# LightBoard_v1_0.net
KiCad netlist of a schematic drawn in Altium Designer
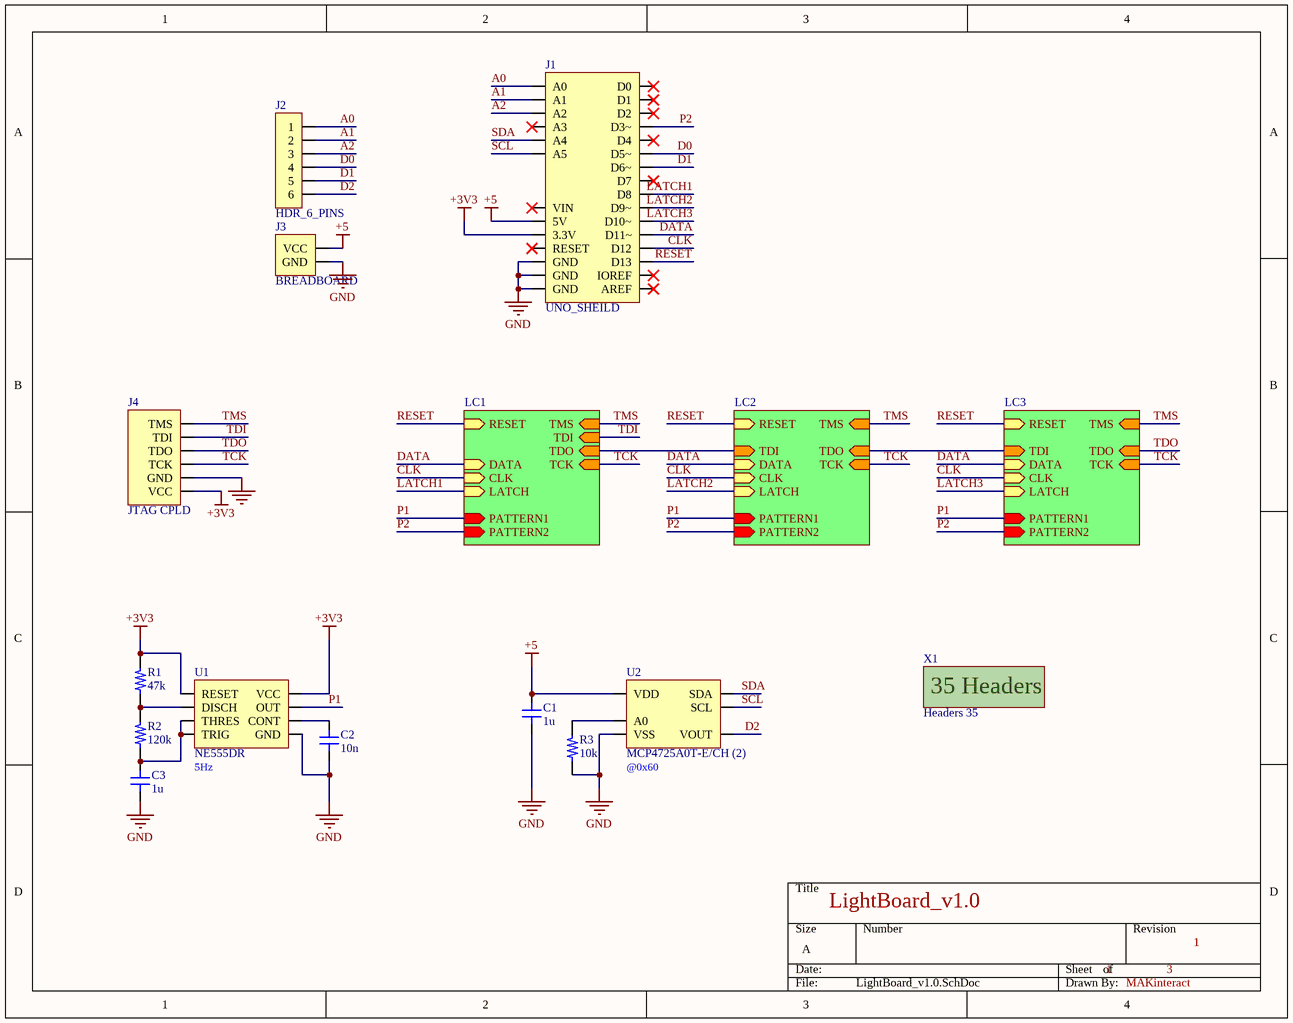
[diagram p0: LightBoard_v1.0.SchDoc]

(export (version "E")
  (design (tool "Eeschema 10.0.6"))
  (components
    (comp (ref "C1")
      (value "1u")
      (fields
        (field (name "MANUFACTURER") "Yageo")
        (field (name "MANUFACTURER PART NUMBER") "CC0805ZRY5V8BB105")
        (field (name "TOLERANCE") "80%")
      )
      (libsource (lib "LightBoard_v1.0") (part "C0805_1u"))
    )
    (comp (ref "C2")
      (value "10n")
      (description "Cap Ceramic 0.01uF 10V X7R 10% SMD 0402 125C Paper T/R")
      (fields
        (field (name "MANUFACTURER") "Yageo")
        (field (name "MANUFACTURER PART NUMBER") "CC0402KRX7R6BB103")
      )
      (libsource (lib "LightBoard_v1.0") (part "C0402_10n"))
    )
    (comp (ref "C3")
      (value "1u")
      (fields
        (field (name "MANUFACTURER") "Yageo")
        (field (name "MANUFACTURER PART NUMBER") "CC0805ZRY5V8BB105")
        (field (name "TOLERANCE") "80%")
      )
      (libsource (lib "LightBoard_v1.0") (part "C0805_1u"))
    )
    (comp (ref "J1")
      (value "UNO_SHEILD")
      (footprint "ARDUINO_UNO_SHIELD")
      (description "Arduino UNO shield")
      (fields (field (name "MANUFACTURER") "Arduino") (field (name "MANUFACTURER PART NUMBER") "A000073"))
      (libsource (lib "LightBoard_v1.0") (part "ARDUINO_UNO_SHIELD"))
    )
    (comp (ref "J2")
      (value "HDR_6_PINS")
      (description "Sockets to connect to Arduino pins")
      (libsource (lib "LightBoard_v1.0") (part "H_ARDUPINS"))
    )
    (comp (ref "J3")
      (value "BREADBOARD")
      (description "26*2 ROWS")
      (libsource (lib "LightBoard_v1.0") (part "BREADBOARD"))
    )
    (comp (ref "J4")
      (value "JTAG CPLD")
      (description "Socket to connect to JTAG")
      (libsource (lib "LightBoard_v1.0") (part "H_JTAG"))
    )
    (comp (ref "R1")
      (value "47k")
      (fields
        (field (name "MANUFACTURER") "Yageo")
        (field (name "MANUFACTURER PART NUMBER") "RC0402JR-0747KL")
        (field (name "TOLERANCE") "5%")
      )
      (libsource (lib "LightBoard_v1.0") (part "R0402_47K"))
    )
    (comp (ref "R2")
      (value "120k")
      (description "RES SMD 120K OHM 5% 1/16W 0402")
      (fields
        (field (name "MANUFACTURER") "Yageo")
        (field (name "MANUFACTURER PART NUMBER") "RC0402JR-07120KL")
      )
      (libsource (lib "LightBoard_v1.0") (part "R0402_120K"))
    )
    (comp (ref "R3")
      (value "10k")
      (description "RES SMD 10K OHM 1% 1/16W 0402")
      (fields
        (field (name "MANUFACTURER") "Yageo")
        (field (name "MANUFACTURER PART NUMBER") "RC0402FR-0710KP")
      )
      (libsource (lib "LightBoard_v1.0") (part "R0402_10K"))
    )
    (comp (ref "U1")
      (value "NE555DR")
      (description "TEXAS INSTRUMENTS         NE555DR.             TIMER, SINGLE, 500KHZ, 16V, SOIC-8")
      (fields (field (name "MANUFACTURER") "Texas Instruments"))
      (libsource (lib "LightBoard_v1.0") (part "555"))
    )
    (comp (ref "U2")
      (value "MCP4725A0T-E/CH (2)")
      (footprint "SOT23-6")
      (description "DAC 1-CH Resistor-String 12-bit 6-Pin SOT-23A T/R")
      (fields
        (field (name "MANUFACTURER") "Microchip")
        (field (name "MANUFACTURER PART NUMBER") "MCP4725A0T-E/CH")
      )
      (libsource (lib "LightBoard_v1.0") (part "MCP4725A0T"))
    )
    (comp (ref "X1")
      (value "Headers 35")
      (description "Conn Header Vert 35POS 2.54MM")
      (fields
        (field (name "MANUFACTURER") "Preci-Dip")
        (field (name "MANUFACTURER PART NUMBER") "890-70-035-10-001101")
      )
      (libsource (lib "LightBoard_v1.0") (part "M_Headers35"))
    )
  )
  (nets
    (net (code "1") (name "+3V3") (class "Default")
      (node (ref "J1") (pin "27") (pinfunction "3.3V_27") (pintype "passive"))
      (node (ref "J4") (pin "6") (pinfunction "VCC_6") (pintype "passive"))
      (node (ref "R1") (pin "2") (pinfunction "2_2") (pintype "passive"))
      (node (ref "U1") (pin "4") (pinfunction "RESET_4") (pintype "passive"))
      (node (ref "U1") (pin "8") (pinfunction "VCC_8") (pintype "passive"))
    )
    (net (code "2") (name "+5") (class "Default")
      (node (ref "C1") (pin "2") (pinfunction "2_2") (pintype "passive"))
      (node (ref "J1") (pin "26") (pinfunction "5V_26") (pintype "passive"))
      (node (ref "J3") (pin "1") (pinfunction "VCC_1") (pintype "passive"))
      (node (ref "U2") (pin "3") (pinfunction "VDD_3") (pintype "passive"))
    )
    (net (code "3") (name "/A0") (class "Default")
      (node (ref "J1") (pin "22") (pinfunction "A0_22") (pintype "passive"))
      (node (ref "J2") (pin "1") (pinfunction "1_1") (pintype "passive"))
    )
    (net (code "4") (name "/A1") (class "Default")
      (node (ref "J1") (pin "21") (pinfunction "A1_21") (pintype "passive"))
      (node (ref "J2") (pin "2") (pinfunction "2_2") (pintype "passive"))
    )
    (net (code "5") (name "/A2") (class "Default")
      (node (ref "J1") (pin "20") (pinfunction "A2_20") (pintype "passive"))
      (node (ref "J2") (pin "3") (pinfunction "3_3") (pintype "passive"))
    )
    (net (code "6") (name "/CLK") (class "Default")
      (node (ref "J1") (pin "13") (pinfunction "D12_13") (pintype "passive"))
    )
    (net (code "7") (name "/D0") (class "Default")
      (node (ref "J1") (pin "6") (pinfunction "D5~_6") (pintype "passive"))
      (node (ref "J2") (pin "4") (pinfunction "4_4") (pintype "passive"))
    )
    (net (code "8") (name "/D1") (class "Default")
      (node (ref "J1") (pin "7") (pinfunction "D6~_7") (pintype "passive"))
      (node (ref "J2") (pin "5") (pinfunction "5_5") (pintype "passive"))
    )
    (net (code "9") (name "/D2") (class "Default")
      (node (ref "J2") (pin "6") (pinfunction "6_6") (pintype "passive"))
      (node (ref "U2") (pin "1") (pinfunction "VOUT_1") (pintype "passive"))
    )
    (net (code "10") (name "/DATA") (class "Default")
      (node (ref "J1") (pin "12") (pinfunction "D11~_12") (pintype "passive"))
    )
    (net (code "11") (name "/LATCH1") (class "Default")
      (node (ref "J1") (pin "9") (pinfunction "D8_9") (pintype "passive"))
    )
    (net (code "12") (name "/LATCH2") (class "Default")
      (node (ref "J1") (pin "10") (pinfunction "D9~_10") (pintype "passive"))
    )
    (net (code "13") (name "/LATCH3") (class "Default")
      (node (ref "J1") (pin "11") (pinfunction "D10~_11") (pintype "passive"))
    )
    (net (code "14") (name "/P1") (class "Default")
      (node (ref "U1") (pin "3") (pinfunction "OUT_3") (pintype "passive"))
    )
    (net (code "15") (name "/P2") (class "Default")
      (node (ref "J1") (pin "4") (pinfunction "D3~_4") (pintype "passive"))
    )
    (net (code "16") (name "/RESET") (class "Default")
      (node (ref "J1") (pin "14") (pinfunction "D13_14") (pintype "passive"))
    )
    (net (code "17") (name "/SCL") (class "Default")
      (node (ref "J1") (pin "17") (pinfunction "A5_17") (pintype "passive"))
      (node (ref "U2") (pin "5") (pinfunction "SCL_5") (pintype "passive"))
    )
    (net (code "18") (name "/SDA") (class "Default")
      (node (ref "J1") (pin "18") (pinfunction "A4_18") (pintype "passive"))
      (node (ref "U2") (pin "4") (pinfunction "SDA_4") (pintype "passive"))
    )
    (net (code "19") (name "/TCK") (class "Default")
      (node (ref "J4") (pin "4") (pinfunction "TCK_4") (pintype "passive"))
    )
    (net (code "20") (name "/TDI") (class "Default")
      (node (ref "J4") (pin "2") (pinfunction "TDI_2") (pintype "passive"))
    )
    (net (code "23") (name "/TDO") (class "Default")
      (node (ref "J4") (pin "3") (pinfunction "TDO_3") (pintype "passive"))
    )
    (net (code "24") (name "/TMS") (class "Default")
      (node (ref "J4") (pin "1") (pinfunction "TMS_1") (pintype "passive"))
    )
    (net (code "25") (name "GND") (class "Default")
      (node (ref "C1") (pin "1") (pinfunction "1_1") (pintype "passive"))
      (node (ref "C2") (pin "1") (pinfunction "1_1") (pintype "passive"))
      (node (ref "C3") (pin "1") (pinfunction "1_1") (pintype "passive"))
      (node (ref "J1") (pin "15") (pinfunction "GND_15") (pintype "passive"))
      (node (ref "J1") (pin "24") (pinfunction "GND_24") (pintype "passive"))
      (node (ref "J1") (pin "25") (pinfunction "GND_25") (pintype "passive"))
      (node (ref "J3") (pin "2") (pinfunction "GND_2") (pintype "passive"))
      (node (ref "J4") (pin "5") (pinfunction "GND_5") (pintype "passive"))
      (node (ref "R3") (pin "1") (pinfunction "1_1") (pintype "passive"))
      (node (ref "U1") (pin "1") (pinfunction "GND_1") (pintype "passive"))
      (node (ref "U2") (pin "2") (pinfunction "VSS_2") (pintype "passive"))
    )
    (net (code "26") (name "Net-(U1-CONT)") (class "Default")
      (node (ref "C2") (pin "2") (pinfunction "2_2") (pintype "passive"))
      (node (ref "U1") (pin "5") (pinfunction "CONT_5") (pintype "passive"))
    )
    (net (code "27") (name "Net-(U1-DISCH)") (class "Default")
      (node (ref "R1") (pin "1") (pinfunction "1_1") (pintype "passive"))
      (node (ref "R2") (pin "2") (pinfunction "2_2") (pintype "passive"))
      (node (ref "U1") (pin "7") (pinfunction "DISCH_7") (pintype "passive"))
    )
    (net (code "28") (name "Net-(U1-THRES)") (class "Default")
      (node (ref "C3") (pin "2") (pinfunction "2_2") (pintype "passive"))
      (node (ref "R2") (pin "1") (pinfunction "1_1") (pintype "passive"))
      (node (ref "U1") (pin "2") (pinfunction "TRIG_2") (pintype "passive"))
      (node (ref "U1") (pin "6") (pinfunction "THRES_6") (pintype "passive"))
    )
    (net (code "29") (name "Net-(U2-A0)") (class "Default")
      (node (ref "R3") (pin "2") (pinfunction "2_2") (pintype "passive"))
      (node (ref "U2") (pin "6") (pinfunction "A0_6") (pintype "passive"))
    )
    (net (code "30") (name "unconnected-(J1-A3-Pad19)") (class "Default")
      (node (ref "J1") (pin "19") (pinfunction "A3_19") (pintype "passive+no_connect"))
    )
    (net (code "31") (name "unconnected-(J1-AREF-Pad16)") (class "Default")
      (node (ref "J1") (pin "16") (pinfunction "AREF_16") (pintype "passive+no_connect"))
    )
    (net (code "32") (name "unconnected-(J1-D0-Pad1)") (class "Default")
      (node (ref "J1") (pin "1") (pinfunction "D0_1") (pintype "passive+no_connect"))
    )
    (net (code "33") (name "unconnected-(J1-D1-Pad2)") (class "Default")
      (node (ref "J1") (pin "2") (pinfunction "D1_2") (pintype "passive+no_connect"))
    )
    (net (code "34") (name "unconnected-(J1-D2-Pad3)") (class "Default")
      (node (ref "J1") (pin "3") (pinfunction "D2_3") (pintype "passive+no_connect"))
    )
    (net (code "35") (name "unconnected-(J1-D4-Pad5)") (class "Default")
      (node (ref "J1") (pin "5") (pinfunction "D4_5") (pintype "passive+no_connect"))
    )
    (net (code "36") (name "unconnected-(J1-D7-Pad8)") (class "Default")
      (node (ref "J1") (pin "8") (pinfunction "D7_8") (pintype "passive+no_connect"))
    )
    (net (code "37") (name "unconnected-(J1-IOREF-Pad29)") (class "Default")
      (node (ref "J1") (pin "29") (pinfunction "IOREF_29") (pintype "passive+no_connect"))
    )
    (net (code "38") (name "unconnected-(J1-RESET-Pad28)") (class "Default")
      (node (ref "J1") (pin "28") (pinfunction "RESET_28") (pintype "passive+no_connect"))
    )
    (net (code "39") (name "unconnected-(J1-VIN-Pad23)") (class "Default")
      (node (ref "J1") (pin "23") (pinfunction "VIN_23") (pintype "passive+no_connect"))
    )
  )
)
